# flasher.net
KiCad netlist of a schematic drawn in EAGLE
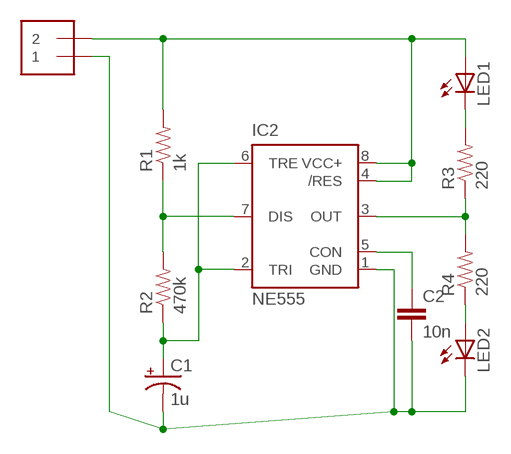
[diagram p0: schematic, sheet 1]

(export (version "E")
  (design (tool "Eeschema 10.0.6"))
  (components
    (comp (ref "C1")
      (value "1u")
      (footprint "eagle-import:CPOL-RADIAL-10UF-25V")
      (libsource (lib "eagle-import") (part "CAP_POLPTH2"))
    )
    (comp (ref "C2")
      (value "10n")
      (footprint "eagle-import:CAP-PTH-SMALL")
      (libsource (lib "eagle-import") (part "CAPPTH"))
    )
    (comp (ref "IC2")
      (value "NE555")
      (footprint "eagle-import:DIL-08")
      (fields (field (name "MF") "Arrow Electronics") (field (name "MPN") "NE555N"))
      (libsource (lib "eagle-import") (part "NE555"))
    )
    (comp (ref "J1")
      (value "1X2-3.5MM")
      (footprint "eagle-import:1X2-3.5MM")
      (libsource (lib "eagle-import") (part "1X2-3.5MM"))
    )
    (comp (ref "LED1")
      (value "LED5MM")
      (footprint "eagle-import:LED5MM")
      (libsource (lib "eagle-import") (part "LED5MM"))
    )
    (comp (ref "LED2")
      (value "LED5MM")
      (footprint "eagle-import:LED5MM")
      (libsource (lib "eagle-import") (part "LED5MM"))
    )
    (comp (ref "R1")
      (value "1k")
      (footprint "eagle-import:AXIAL-0.3")
      (libsource (lib "eagle-import") (part "RESISTORAXIAL-0.3"))
    )
    (comp (ref "R2")
      (value "470k")
      (footprint "eagle-import:AXIAL-0.3")
      (libsource (lib "eagle-import") (part "RESISTORAXIAL-0.3"))
    )
    (comp (ref "R3")
      (value "220")
      (footprint "eagle-import:AXIAL-0.3")
      (libsource (lib "eagle-import") (part "RESISTORAXIAL-0.3"))
    )
    (comp (ref "R4")
      (value "220")
      (footprint "eagle-import:AXIAL-0.3")
      (libsource (lib "eagle-import") (part "RESISTORAXIAL-0.3"))
    )
  )
  (nets
    (net (code "1") (name "Net-(C1-+)") (class "Default")
      (node (ref "C1") (pin "1") (pinfunction "+_1") (pintype "passive"))
      (node (ref "IC2") (pin "2") (pinfunction "TRI_2") (pintype "input"))
      (node (ref "IC2") (pin "6") (pinfunction "TRE_6") (pintype "input"))
      (node (ref "R2") (pin "P$1") (pinfunction "1_P$1") (pintype "passive"))
    )
    (net (code "2") (name "Net-(C1--)") (class "Default")
      (node (ref "C1") (pin "2") (pinfunction "-_2") (pintype "passive"))
      (node (ref "C2") (pin "2") (pinfunction "2_2") (pintype "passive"))
      (node (ref "IC2") (pin "1") (pinfunction "GND_1") (pintype "power_in"))
      (node (ref "J1") (pin "1") (pinfunction "1_1") (pintype "passive"))
      (node (ref "LED2") (pin "K") (pinfunction "C_K") (pintype "passive"))
    )
    (net (code "3") (name "Net-(IC2-CON)") (class "Default")
      (node (ref "C2") (pin "1") (pinfunction "1_1") (pintype "passive"))
      (node (ref "IC2") (pin "5") (pinfunction "CON_5") (pintype "input"))
    )
    (net (code "4") (name "Net-(IC2-DIS)") (class "Default")
      (node (ref "IC2") (pin "7") (pinfunction "DIS_7") (pintype "input"))
      (node (ref "R1") (pin "P$1") (pinfunction "1_P$1") (pintype "passive"))
      (node (ref "R2") (pin "P$2") (pinfunction "2_P$2") (pintype "passive"))
    )
    (net (code "5") (name "Net-(IC2-OUT)") (class "Default")
      (node (ref "IC2") (pin "3") (pinfunction "OUT_3") (pintype "output"))
      (node (ref "R3") (pin "P$1") (pinfunction "1_P$1") (pintype "passive"))
      (node (ref "R4") (pin "P$2") (pinfunction "2_P$2") (pintype "passive"))
    )
    (net (code "6") (name "Net-(IC2-VCC+)") (class "Default")
      (node (ref "IC2") (pin "4") (pinfunction "/RES_4") (pintype "input"))
      (node (ref "IC2") (pin "8") (pinfunction "VCC+_8") (pintype "power_in"))
      (node (ref "J1") (pin "2") (pinfunction "2_2") (pintype "passive"))
      (node (ref "LED1") (pin "A") (pinfunction "A_A") (pintype "passive"))
      (node (ref "R1") (pin "P$2") (pinfunction "2_P$2") (pintype "passive"))
    )
    (net (code "7") (name "Net-(LED1-C)") (class "Default")
      (node (ref "LED1") (pin "K") (pinfunction "C_K") (pintype "passive"))
      (node (ref "R3") (pin "P$2") (pinfunction "2_P$2") (pintype "passive"))
    )
    (net (code "8") (name "Net-(R4-1)") (class "Default")
      (node (ref "LED2") (pin "A") (pinfunction "A_A") (pintype "passive"))
      (node (ref "R4") (pin "P$1") (pinfunction "1_P$1") (pintype "passive"))
    )
  )
)
